# LG_TRACKER_LoRa_Module.net
KiCad netlist of a schematic drawn in Altium Designer
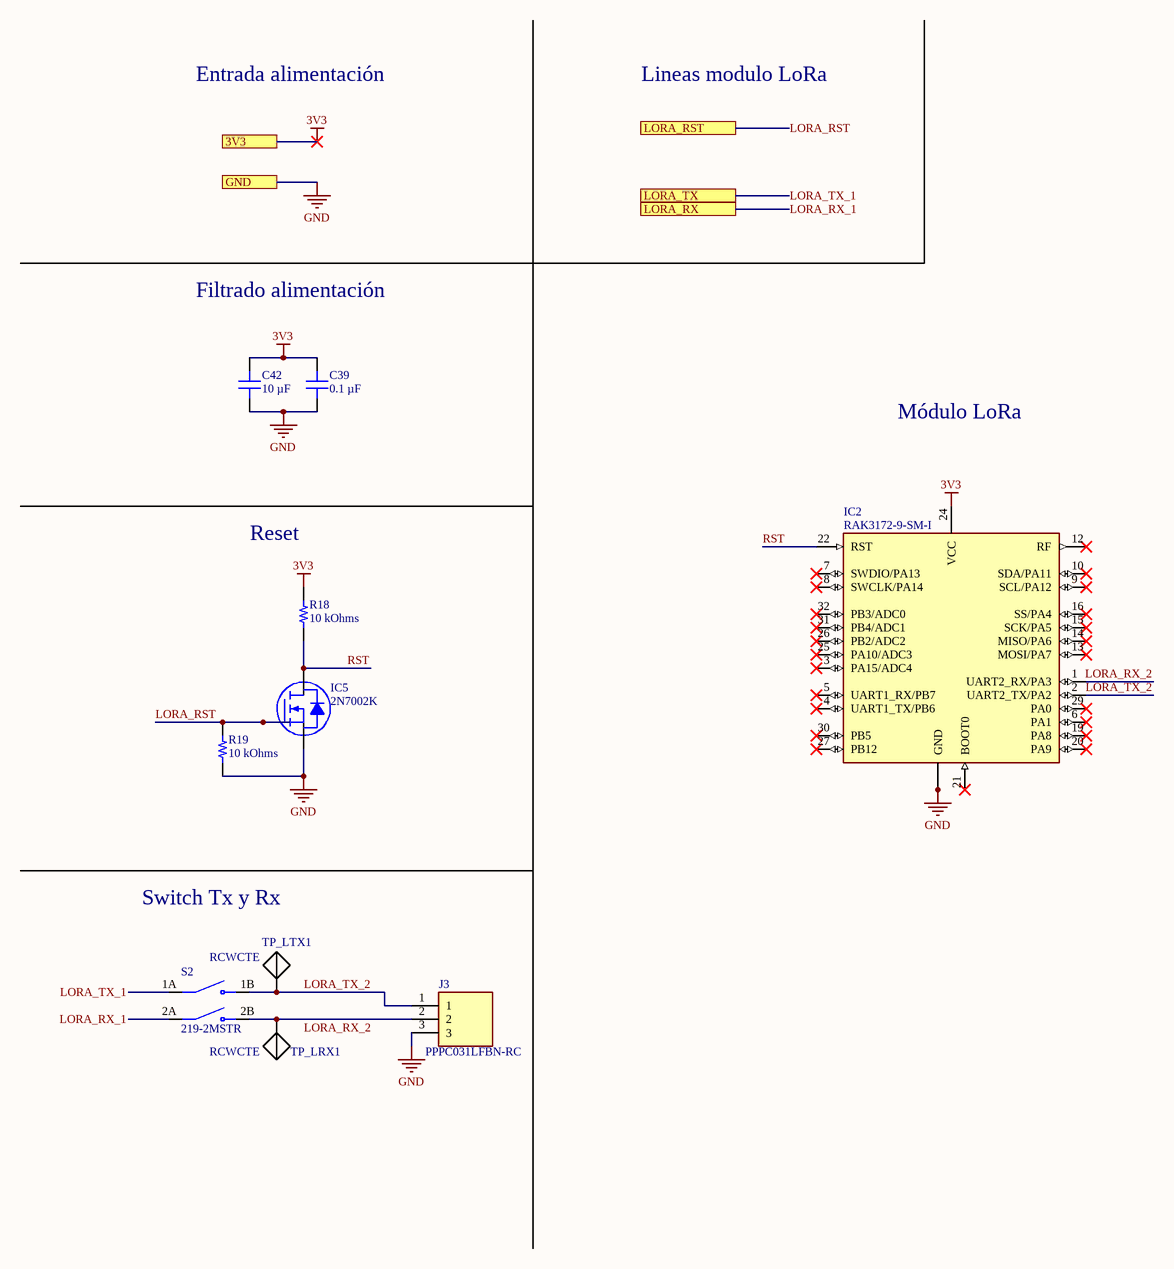
[diagram p0: LG_TRACKER_LoRa_Module.SchDoc]

(export (version "E")
  (design (tool "Eeschema 10.0.6"))
  (components
    (comp (ref "C39")
      (value "0.1 µF")
      (footprint "PCB - CAPACITOR - MLCC - MURATA GRM155 0402_1005:MURATA GRM155 0402_1005")
      (description "CAP CER 0.1UF 50V X7R 0402")
      (fields
        (field (name "PART NUMBER") "GRM155R71H104KE14D")
        (field (name "MANUFACTURER") "Murata Electronics")
      )
      (libsource (lib "Celestial Altium Library - altium_library") (part "Capacitor"))
    )
    (comp (ref "C42")
      (value "10 µF")
      (footprint "CAP 0805_2012")
      (description "CAP CER 10UF 16V X5R 0805")
      (fields
        (field (name "PART NUMBER") "CL21A106KOQNNNE")
        (field (name "MANUFACTURER") "Samsung Electro-Mechanics")
      )
      (libsource (lib "Celestial Altium Library - altium_library") (part "Capacitor"))
    )
    (comp (ref "IC2")
      (value "RAK3172-9-SM-I")
      (footprint "RAK3172-9-SM-I")
      (description "LoRaWAN module from RAK")
      (fields (field (name "MF") "Shenzhen RAKwireless Technology Co.,Ltd."))
      (libsource (lib "DIN_DC_Base_Board_components") (part "RAK3172-9-SM-I"))
    )
    (comp (ref "IC5")
      (value "2N7002K")
      (footprint "SOT23")
      (description "MOSFET N-CH 60V 300MA SOT23")
      (fields (field (name "MANUFACTURER") "ON Semiconductor"))
      (libsource (lib "Celestial Altium Library - altium_library") (part "ON SEMI MOSFET N-CH SOT-23-3"))
    )
    (comp (ref "J3")
      (value "PPPC031LFBN-RC")
      (footprint "PPPC031LFBN-RC")
      (description "Connector")
      (libsource (lib "DIN_DC_Base_Board_components") (part "PPPC031LFBN-RC"))
    )
    (comp (ref "R18")
      (value "10 kOhms")
      (footprint "RES 0603_1608")
      (description "RES 10K OHM 1% 1/10W 0603")
      (fields (field (name "PART NUMBER") "RC0603FR-0710KL") (field (name "MANUFACTURER") "Yageo"))
      (libsource (lib "Celestial Altium Library - altium_library") (part "Resistor"))
    )
    (comp (ref "R19")
      (value "10 kOhms")
      (footprint "RES 0603_1608")
      (description "RES 10K OHM 1% 1/10W 0603")
      (fields (field (name "PART NUMBER") "RC0603FR-0710KL") (field (name "MANUFACTURER") "Yageo"))
      (libsource (lib "Celestial Altium Library - altium_library") (part "Resistor"))
    )
    (comp (ref "S2")
      (value "219-2MSTR")
      (footprint "SW_219-2MSTR")
      (description "Dip Switch SPST 2 Position Surface Mount Slide (Standard) Actuator 100mA 20VDC")
      (fields (field (name "MF") "CTS Electrocomponents"))
      (libsource (lib "DIN_DC_Base_Board_components") (part "219-2MSTR"))
    )
    (comp (ref "TP_LRX1")
      (value "RCWCTE")
      (footprint "RCWCTE")
      (description "- PC Test Point - - Plating Surface Mount Mounting Type")
      (fields (field (name "MF") "KOA Speer") (field (name "DIGI-KEY_PART_NUMBER") "2019-RCWCTETR-ND"))
      (libsource (lib "DIN_DC_Base_Board_components") (part "RCWCTE"))
    )
    (comp (ref "TP_LTX1")
      (value "RCWCTE")
      (footprint "RCWCTE")
      (description "- PC Test Point - - Plating Surface Mount Mounting Type")
      (fields (field (name "MF") "KOA Speer") (field (name "DIGI-KEY_PART_NUMBER") "2019-RCWCTETR-ND"))
      (libsource (lib "DIN_DC_Base_Board_components") (part "RCWCTE"))
    )
  )
  (nets
    (net (code "1") (name "/LORA_RST") (class "Default")
      (node (ref "IC5") (pin "1") (pinfunction "G_1") (pintype "passive"))
      (node (ref "R19") (pin "1") (pinfunction "1_1") (pintype "passive"))
    )
    (net (code "2") (name "/LORA_RX_1") (class "Default")
      (node (ref "S2") (pin "2A") (pinfunction "COM2_2A") (pintype "passive"))
    )
    (net (code "3") (name "/LORA_RX_2") (class "Default")
      (node (ref "IC2") (pin "1") (pinfunction "UART2_RX/PA3_1") (pintype "bidirectional"))
      (node (ref "J3") (pin "2") (pinfunction "2_2") (pintype "passive"))
      (node (ref "S2") (pin "2B") (pinfunction "NO2_2B") (pintype "passive"))
      (node (ref "TP_LRX1") (pin "1") (pinfunction "TP_1") (pintype "passive"))
    )
    (net (code "4") (name "/LORA_TX_1") (class "Default")
      (node (ref "S2") (pin "1A") (pinfunction "COM1_1A") (pintype "passive"))
    )
    (net (code "5") (name "/LORA_TX_2") (class "Default")
      (node (ref "IC2") (pin "2") (pinfunction "UART2_TX/PA2_2") (pintype "bidirectional"))
      (node (ref "J3") (pin "1") (pinfunction "1_1") (pintype "passive"))
      (node (ref "S2") (pin "1B") (pinfunction "NO1_1B") (pintype "passive"))
      (node (ref "TP_LTX1") (pin "1") (pinfunction "TP_1") (pintype "passive"))
    )
    (net (code "6") (name "/RST") (class "Default")
      (node (ref "IC2") (pin "22") (pinfunction "RST_22") (pintype "input"))
      (node (ref "IC5") (pin "3") (pinfunction "D_3") (pintype "passive"))
      (node (ref "R18") (pin "2") (pinfunction "2_2") (pintype "passive"))
    )
    (net (code "7") (name "3V3") (class "Default")
      (node (ref "C39") (pin "1") (pinfunction "1_1") (pintype "passive"))
      (node (ref "C42") (pin "2") (pinfunction "2_2") (pintype "passive"))
      (node (ref "IC2") (pin "24") (pinfunction "VCC_24") (pintype "power_in"))
      (node (ref "R18") (pin "1") (pinfunction "1_1") (pintype "passive"))
    )
    (net (code "8") (name "GND") (class "Default")
      (node (ref "C39") (pin "2") (pinfunction "2_2") (pintype "passive"))
      (node (ref "C42") (pin "1") (pinfunction "1_1") (pintype "passive"))
      (node (ref "IC2") (pin "11") (pinfunction "GND_11") (pintype "power_in"))
      (node (ref "IC2") (pin "17") (pinfunction "GND_17") (pintype "power_in"))
      (node (ref "IC2") (pin "18") (pinfunction "GND_18") (pintype "power_in"))
      (node (ref "IC2") (pin "23") (pinfunction "GND_23") (pintype "power_in"))
      (node (ref "IC2") (pin "28") (pinfunction "GND_28") (pintype "power_in"))
      (node (ref "IC5") (pin "2") (pinfunction "S_2") (pintype "passive"))
      (node (ref "J3") (pin "3") (pinfunction "3_3") (pintype "passive"))
      (node (ref "R19") (pin "2") (pinfunction "2_2") (pintype "passive"))
    )
    (net (code "9") (name "unconnected-(IC2-BOOT0-Pad21)") (class "Default")
      (node (ref "IC2") (pin "21") (pinfunction "BOOT0_21") (pintype "input+no_connect"))
    )
    (net (code "10") (name "unconnected-(IC2-MISO{slash}PA6-Pad14)") (class "Default")
      (node (ref "IC2") (pin "14") (pinfunction "MISO/PA6_14") (pintype "bidirectional+no_connect"))
    )
    (net (code "11") (name "unconnected-(IC2-MOSI{slash}PA7-Pad13)") (class "Default")
      (node (ref "IC2") (pin "13") (pinfunction "MOSI/PA7_13") (pintype "bidirectional+no_connect"))
    )
    (net (code "12") (name "unconnected-(IC2-PA0-Pad29)") (class "Default")
      (node (ref "IC2") (pin "29") (pinfunction "PA0_29") (pintype "bidirectional+no_connect"))
    )
    (net (code "13") (name "unconnected-(IC2-PA1-Pad6)") (class "Default")
      (node (ref "IC2") (pin "6") (pinfunction "PA1_6") (pintype "bidirectional+no_connect"))
    )
    (net (code "14") (name "unconnected-(IC2-PA8-Pad19)") (class "Default")
      (node (ref "IC2") (pin "19") (pinfunction "PA8_19") (pintype "bidirectional+no_connect"))
    )
    (net (code "15") (name "unconnected-(IC2-PA9-Pad20)") (class "Default")
      (node (ref "IC2") (pin "20") (pinfunction "PA9_20") (pintype "bidirectional+no_connect"))
    )
    (net (code "16") (name "unconnected-(IC2-PA10{slash}ADC3-Pad25)") (class "Default")
      (node (ref "IC2") (pin "25") (pinfunction "PA10/ADC3_25") (pintype "bidirectional+no_connect"))
    )
    (net (code "17") (name "unconnected-(IC2-PA15{slash}ADC4-Pad3)") (class "Default")
      (node (ref "IC2") (pin "3") (pinfunction "PA15/ADC4_3") (pintype "bidirectional+no_connect"))
    )
    (net (code "18") (name "unconnected-(IC2-PB2{slash}ADC2-Pad26)") (class "Default")
      (node (ref "IC2") (pin "26") (pinfunction "PB2/ADC2_26") (pintype "bidirectional+no_connect"))
    )
    (net (code "19") (name "unconnected-(IC2-PB3{slash}ADC0-Pad32)") (class "Default")
      (node (ref "IC2") (pin "32") (pinfunction "PB3/ADC0_32") (pintype "bidirectional+no_connect"))
    )
    (net (code "20") (name "unconnected-(IC2-PB4{slash}ADC1-Pad31)") (class "Default")
      (node (ref "IC2") (pin "31") (pinfunction "PB4/ADC1_31") (pintype "bidirectional+no_connect"))
    )
    (net (code "21") (name "unconnected-(IC2-PB5-Pad30)") (class "Default")
      (node (ref "IC2") (pin "30") (pinfunction "PB5_30") (pintype "bidirectional+no_connect"))
    )
    (net (code "22") (name "unconnected-(IC2-PB12-Pad27)") (class "Default")
      (node (ref "IC2") (pin "27") (pinfunction "PB12_27") (pintype "bidirectional+no_connect"))
    )
    (net (code "23") (name "unconnected-(IC2-RF-Pad12)") (class "Default")
      (node (ref "IC2") (pin "12") (pinfunction "RF_12") (pintype "output+no_connect"))
    )
    (net (code "24") (name "unconnected-(IC2-SCK{slash}PA5-Pad15)") (class "Default")
      (node (ref "IC2") (pin "15") (pinfunction "SCK/PA5_15") (pintype "bidirectional+no_connect"))
    )
    (net (code "25") (name "unconnected-(IC2-SCL{slash}PA12-Pad9)") (class "Default")
      (node (ref "IC2") (pin "9") (pinfunction "SCL/PA12_9") (pintype "bidirectional+no_connect"))
    )
    (net (code "26") (name "unconnected-(IC2-SDA{slash}PA11-Pad10)") (class "Default")
      (node (ref "IC2") (pin "10") (pinfunction "SDA/PA11_10") (pintype "bidirectional+no_connect"))
    )
    (net (code "27") (name "unconnected-(IC2-SS{slash}PA4-Pad16)") (class "Default")
      (node (ref "IC2") (pin "16") (pinfunction "SS/PA4_16") (pintype "bidirectional+no_connect"))
    )
    (net (code "28") (name "unconnected-(IC2-SWCLK{slash}PA14-Pad8)") (class "Default")
      (node (ref "IC2") (pin "8") (pinfunction "SWCLK/PA14_8") (pintype "bidirectional+no_connect"))
    )
    (net (code "29") (name "unconnected-(IC2-SWDIO{slash}PA13-Pad7)") (class "Default")
      (node (ref "IC2") (pin "7") (pinfunction "SWDIO/PA13_7") (pintype "bidirectional+no_connect"))
    )
    (net (code "30") (name "unconnected-(IC2-UART1_RX{slash}PB7-Pad5)") (class "Default")
      (node (ref "IC2") (pin "5") (pinfunction "UART1_RX/PB7_5") (pintype "bidirectional+no_connect"))
    )
    (net (code "31") (name "unconnected-(IC2-UART1_TX{slash}PB6-Pad4)") (class "Default")
      (node (ref "IC2") (pin "4") (pinfunction "UART1_TX/PB6_4") (pintype "bidirectional+no_connect"))
    )
  )
)
